# BM833.net
KiCad netlist of a schematic drawn in EAGLE
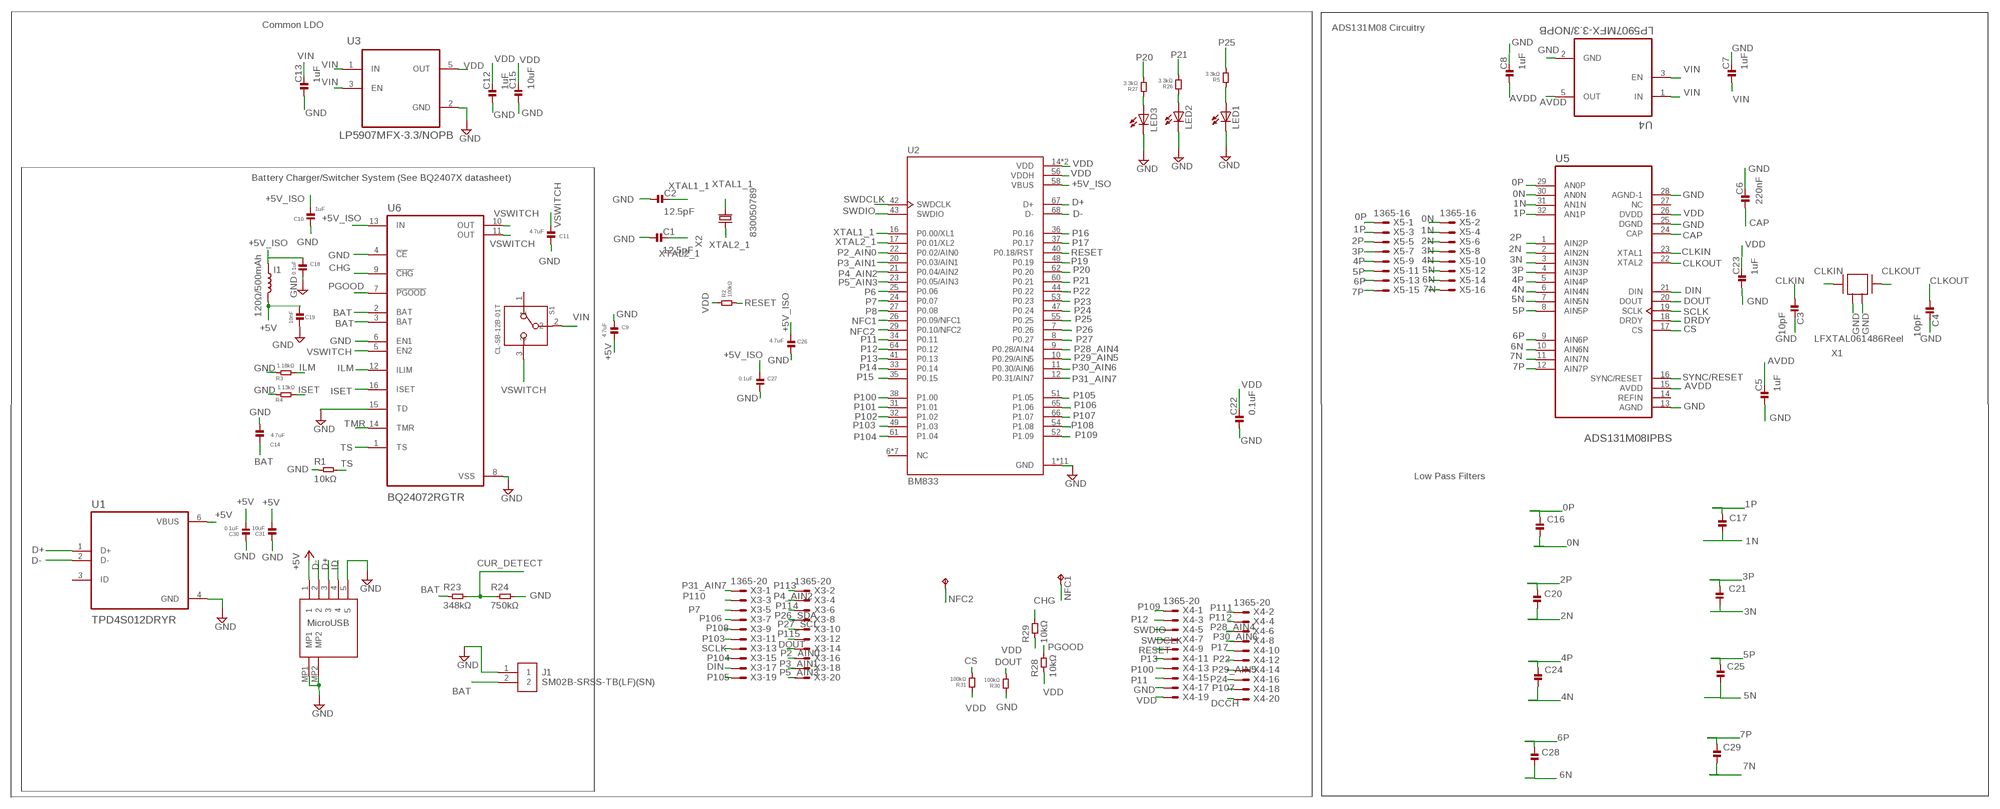
[diagram p0: schematic, sheet 1]

(export (version "E")
  (design (tool "Eeschema 10.0.6"))
  (components
    (comp (ref "C1")
      (value "12.5pF")
      (footprint "eagle-import:0201")
      (libsource (lib "eagle-import") (part "CAPACITOR.0201"))
    )
    (comp (ref "C2")
      (value "12.5pF")
      (footprint "eagle-import:0201")
      (libsource (lib "eagle-import") (part "CAPACITOR.0201"))
    )
    (comp (ref "C3")
      (value "10pF")
      (footprint "eagle-import:0201")
      (libsource (lib "eagle-import") (part "CAPACITOR.0201"))
    )
    (comp (ref "C4")
      (value "10pF")
      (footprint "eagle-import:0201")
      (libsource (lib "eagle-import") (part "CAPACITOR.0201"))
    )
    (comp (ref "C5")
      (value "1uF")
      (footprint "eagle-import:0201")
      (libsource (lib "eagle-import") (part "CAPACITOR.0201"))
    )
    (comp (ref "C6")
      (value "220nF")
      (footprint "eagle-import:0201")
      (libsource (lib "eagle-import") (part "CAPACITOR.0201"))
    )
    (comp (ref "C7")
      (value "1uF")
      (footprint "eagle-import:0201")
      (libsource (lib "eagle-import") (part "CAPACITOR.0201"))
    )
    (comp (ref "C8")
      (value "1uF")
      (footprint "eagle-import:0201")
      (libsource (lib "eagle-import") (part "CAPACITOR.0201"))
    )
    (comp (ref "C9")
      (value "4.7uF")
      (footprint "eagle-import:0201")
      (libsource (lib "eagle-import") (part "CAPACITOR.0201"))
    )
    (comp (ref "C10")
      (value "1uF")
      (footprint "eagle-import:0201")
      (libsource (lib "eagle-import") (part "CAPACITOR.0201"))
    )
    (comp (ref "C11")
      (value "4.7uF")
      (footprint "eagle-import:0201")
      (libsource (lib "eagle-import") (part "CAPACITOR.0201"))
    )
    (comp (ref "C12")
      (value "1uF")
      (footprint "eagle-import:0201")
      (libsource (lib "eagle-import") (part "CAPACITOR.0201"))
    )
    (comp (ref "C13")
      (value "1uF")
      (footprint "eagle-import:0201")
      (libsource (lib "eagle-import") (part "CAPACITOR.0201"))
    )
    (comp (ref "C14")
      (value "4.7uF")
      (footprint "eagle-import:0201")
      (libsource (lib "eagle-import") (part "CAPACITOR.0201"))
    )
    (comp (ref "C15")
      (value "10uF")
      (footprint "eagle-import:0402")
      (libsource (lib "eagle-import") (part "CAPACITOR.0402"))
    )
    (comp (ref "C16")
      (value "100pF")
      (footprint "eagle-import:0201")
      (libsource (lib "eagle-import") (part "CAPACITOR.0201"))
    )
    (comp (ref "C17")
      (value "100pF")
      (footprint "eagle-import:0201")
      (libsource (lib "eagle-import") (part "CAPACITOR.0201"))
    )
    (comp (ref "C18")
      (value "0.1uF")
      (footprint "eagle-import:0201")
      (libsource (lib "eagle-import") (part "CAPACITOR.0201"))
    )
    (comp (ref "C19")
      (value "10nF")
      (footprint "eagle-import:0201")
      (libsource (lib "eagle-import") (part "CAPACITOR.0201"))
    )
    (comp (ref "C20")
      (value "100pF")
      (footprint "eagle-import:0201")
      (libsource (lib "eagle-import") (part "CAPACITOR.0201"))
    )
    (comp (ref "C21")
      (value "100pF")
      (footprint "eagle-import:0201")
      (libsource (lib "eagle-import") (part "CAPACITOR.0201"))
    )
    (comp (ref "C22")
      (value "0.1uF")
      (footprint "eagle-import:0201")
      (libsource (lib "eagle-import") (part "CAPACITOR.0201"))
    )
    (comp (ref "C23")
      (value "1uF")
      (footprint "eagle-import:0201")
      (libsource (lib "eagle-import") (part "CAPACITOR.0201"))
    )
    (comp (ref "C24")
      (value "100pF")
      (footprint "eagle-import:0201")
      (libsource (lib "eagle-import") (part "CAPACITOR.0201"))
    )
    (comp (ref "C25")
      (value "100pF")
      (footprint "eagle-import:0201")
      (libsource (lib "eagle-import") (part "CAPACITOR.0201"))
    )
    (comp (ref "C26")
      (value "4.7uF")
      (footprint "eagle-import:0201")
      (libsource (lib "eagle-import") (part "CAPACITOR.0201"))
    )
    (comp (ref "C27")
      (value "0.1uF")
      (footprint "eagle-import:0201")
      (libsource (lib "eagle-import") (part "CAPACITOR.0201"))
    )
    (comp (ref "C28")
      (value "100pF")
      (footprint "eagle-import:0201")
      (libsource (lib "eagle-import") (part "CAPACITOR.0201"))
    )
    (comp (ref "C29")
      (value "100pF")
      (footprint "eagle-import:0201")
      (libsource (lib "eagle-import") (part "CAPACITOR.0201"))
    )
    (comp (ref "C30")
      (value "0.1uF")
      (footprint "eagle-import:0201")
      (libsource (lib "eagle-import") (part "CAPACITOR.0201"))
    )
    (comp (ref "C31")
      (value "10uF")
      (footprint "eagle-import:0402")
      (libsource (lib "eagle-import") (part "CAPACITOR.0402"))
    )
    (comp (ref "I1")
      (value "120Ω/500mAh")
      (footprint "eagle-import:0402_COILCRAFT")
      (fields (field (name "MOUSER_PART") "994-0402HP-12NXGLU"))
      (libsource (lib "eagle-import") (part "12NH-0402"))
    )
    (comp (ref "J1")
      (value "SM02B-SRSS-TB(LF)(SN)")
      (footprint "eagle-import:SM02B-SRSS-TB(LF)(SN)")
      (fields (field (name "MF") "JST Sales"))
      (libsource (lib "eagle-import") (part "SM02B-SRSS-TB(LF)(SN)"))
    )
    (comp (ref "LED1")
      (value "LEDCHIPLED_0603")
      (footprint "eagle-import:CHIPLED_0603")
      (libsource (lib "eagle-import") (part "LEDCHIPLED_0603"))
    )
    (comp (ref "LED2")
      (value "LEDCHIPLED_0603")
      (footprint "eagle-import:CHIPLED_0603")
      (libsource (lib "eagle-import") (part "LEDCHIPLED_0603"))
    )
    (comp (ref "LED3")
      (value "LEDCHIPLED_0603")
      (footprint "eagle-import:CHIPLED_0603")
      (libsource (lib "eagle-import") (part "LEDCHIPLED_0603"))
    )
    (comp (ref "NFC1")
      (value "TPTP14SQ")
      (footprint "eagle-import:TP14SQ")
      (libsource (lib "eagle-import") (part "TPTP14SQ"))
    )
    (comp (ref "NFC2")
      (value "TPTP14SQ")
      (footprint "eagle-import:TP14SQ")
      (libsource (lib "eagle-import") (part "TPTP14SQ"))
    )
    (comp (ref "R1")
      (value "10kΩ")
      (footprint "eagle-import:0201")
      (libsource (lib "eagle-import") (part "RESISTOR.0201"))
    )
    (comp (ref "R2")
      (value "100kΩ")
      (footprint "eagle-import:0201")
      (libsource (lib "eagle-import") (part "RESISTOR.0201"))
    )
    (comp (ref "R3")
      (value "1.18kΩ")
      (footprint "eagle-import:0201")
      (fields (field (name "SPICEPREFIX") "R"))
      (libsource (lib "eagle-import") (part "RESISTOR.0201"))
    )
    (comp (ref "R4")
      (value "1.13kΩ")
      (footprint "eagle-import:0201")
      (libsource (lib "eagle-import") (part "RESISTOR.0201"))
    )
    (comp (ref "R5")
      (value "3.3kΩ")
      (footprint "eagle-import:0201")
      (libsource (lib "eagle-import") (part "RESISTOR.0201"))
    )
    (comp (ref "R23")
      (value "348kΩ")
      (footprint "eagle-import:0201")
      (libsource (lib "eagle-import") (part "RESISTOR.0201"))
    )
    (comp (ref "R24")
      (value "750kΩ")
      (footprint "eagle-import:0201")
      (libsource (lib "eagle-import") (part "RESISTOR.0201"))
    )
    (comp (ref "R26")
      (value "3.3kΩ")
      (footprint "eagle-import:0201")
      (libsource (lib "eagle-import") (part "RESISTOR.0201"))
    )
    (comp (ref "R27")
      (value "3.3kΩ")
      (footprint "eagle-import:0201")
      (libsource (lib "eagle-import") (part "RESISTOR.0201"))
    )
    (comp (ref "R28")
      (value "10kΩ")
      (footprint "eagle-import:0402")
      (libsource (lib "eagle-import") (part "RESISTOR.0402"))
    )
    (comp (ref "R29")
      (value "10kΩ")
      (footprint "eagle-import:0402")
      (libsource (lib "eagle-import") (part "RESISTOR.0402"))
    )
    (comp (ref "R30")
      (value "100kΩ")
      (footprint "eagle-import:0402")
      (libsource (lib "eagle-import") (part "RESISTOR.0402"))
    )
    (comp (ref "R31")
      (value "100kΩ")
      (footprint "eagle-import:0402")
      (libsource (lib "eagle-import") (part "RESISTOR.0402"))
    )
    (comp (ref "S1")
      (value "CL-SB-12B-01T")
      (footprint "eagle-import:CL-SB-12B")
      (fields (field (name "MF") "Nidec Copal"))
      (libsource (lib "eagle-import") (part "CL-SB-12B-01T"))
    )
    (comp (ref "U1")
      (value "TPD4S012DRYR")
      (footprint "eagle-import:PSON50P145X100X60-6N")
      (fields (field (name "MF") "Texas Instruments"))
      (libsource (lib "eagle-import") (part "TPD4S012DRYR"))
    )
    (comp (ref "U2")
      (value "BM833")
      (footprint "eagle-import:XCVR_BM833")
      (fields (field (name "MF") "Fanstel"))
      (libsource (lib "eagle-import") (part "BM833"))
    )
    (comp (ref "U3")
      (value "LP5907MFX-3.3/NOPB")
      (footprint "eagle-import:SOT95P280X145-5N")
      (fields (field (name "MF") "Texas Instruments"))
      (libsource (lib "eagle-import") (part "LP5907MFX-3.3/NOPB"))
    )
    (comp (ref "U4")
      (value "LP5907MFX-3.3/NOPB")
      (footprint "eagle-import:SOT95P280X145-5N")
      (fields (field (name "MF") "Texas Instruments"))
      (libsource (lib "eagle-import") (part "LP5907MFX-3.3/NOPB"))
    )
    (comp (ref "U5")
      (value "ADS131M08IPBS")
      (footprint "eagle-import:QFP50P700X700X120-32N")
      (fields (field (name "MF") "Texas Instruments"))
      (libsource (lib "eagle-import") (part "ADS131M08IPBS"))
    )
    (comp (ref "U6")
      (value "BQ24072RGTR")
      (footprint "eagle-import:QFN50P300X300X100-17N")
      (fields (field (name "MF") "Texas Instruments"))
      (libsource (lib "eagle-import") (part "BQ24072RGTR"))
    )
    (comp (ref "U7")
      (value "DX4R005JJ2R1800")
      (footprint "eagle-import:DX4R005JJ2R1800")
      (fields (field (name "MF") "JAE Electronics"))
      (libsource (lib "eagle-import") (part "DX4R005JJ2R1800"))
    )
    (comp (ref "X1")
      (value "ABM3B-8.000MHZ-B2-T")
      (footprint "eagle-import:ABM3B-8.000MHZ-B2-T")
      (fields
        (field (name "DIGIKEY_PART_NUMBER") "535-9720-2-ND")
        (field (name "MANUFACTURER") "Abracon LLC")
        (field (name "CREATED_BY") "PCBLayout.com")
      )
      (libsource (lib "eagle-import") (part "ABM3B-8.000MHZ-B2-T"))
    )
    (comp (ref "X2")
      (value "FC-12M")
      (footprint "eagle-import:FC-12M")
      (libsource (lib "eagle-import") (part "FC-12M"))
    )
    (comp (ref "X3")
      (value "1365-20")
      (footprint "eagle-import:1365-20")
      (libsource (lib "eagle-import") (part "1365-20"))
    )
    (comp (ref "X4")
      (value "1365-20")
      (footprint "eagle-import:1365-20")
      (libsource (lib "eagle-import") (part "1365-20"))
    )
    (comp (ref "X5")
      (value "1365-16")
      (footprint "eagle-import:1365-16")
      (libsource (lib "eagle-import") (part "1365-16"))
    )
  )
  (nets
    (net (code "1") (name "+5V") (class "Default")
      (node (ref "C19") (pin "2") (pinfunction "2_2") (pintype "bidirectional"))
      (node (ref "C30") (pin "2") (pinfunction "2_2") (pintype "bidirectional"))
      (node (ref "C31") (pin "2") (pinfunction "2_2") (pintype "bidirectional"))
      (node (ref "C9") (pin "2") (pinfunction "2_2") (pintype "bidirectional"))
      (node (ref "I1") (pin "P$2") (pinfunction "2_P$2") (pintype "passive"))
      (node (ref "U1") (pin "6") (pinfunction "VBUS_6") (pintype "power_in"))
      (node (ref "U7") (pin "1") (pinfunction "1_1") (pintype "bidirectional"))
    )
    (net (code "2") (name "+5V_ISO") (class "Default")
      (node (ref "C10") (pin "2") (pinfunction "2_2") (pintype "bidirectional"))
      (node (ref "C18") (pin "1") (pinfunction "1_1") (pintype "bidirectional"))
      (node (ref "C26") (pin "2") (pinfunction "2_2") (pintype "bidirectional"))
      (node (ref "C27") (pin "2") (pinfunction "2_2") (pintype "bidirectional"))
      (node (ref "I1") (pin "P$1") (pinfunction "1_P$1") (pintype "passive"))
      (node (ref "U2") (pin "58") (pinfunction "VBUS_58") (pintype "power_in"))
      (node (ref "U6") (pin "13") (pinfunction "IN_13") (pintype "input"))
    )
    (net (code "3") (name "0N") (class "Default")
      (node (ref "C16") (pin "2") (pinfunction "2_2") (pintype "bidirectional"))
      (node (ref "U5") (pin "30") (pinfunction "AN0N_30") (pintype "bidirectional"))
      (node (ref "X5") (pin "2") (pinfunction "S_2") (pintype "passive"))
    )
    (net (code "4") (name "0P") (class "Default")
      (node (ref "C16") (pin "1") (pinfunction "1_1") (pintype "bidirectional"))
      (node (ref "U5") (pin "29") (pinfunction "AN0P_29") (pintype "bidirectional"))
      (node (ref "X5") (pin "1") (pinfunction "S_1") (pintype "passive"))
    )
    (net (code "5") (name "1N") (class "Default")
      (node (ref "C17") (pin "2") (pinfunction "2_2") (pintype "bidirectional"))
      (node (ref "U5") (pin "31") (pinfunction "AN1N_31") (pintype "bidirectional"))
      (node (ref "X5") (pin "4") (pinfunction "S_4") (pintype "passive"))
    )
    (net (code "6") (name "1P") (class "Default")
      (node (ref "C17") (pin "1") (pinfunction "1_1") (pintype "bidirectional"))
      (node (ref "U5") (pin "32") (pinfunction "AN1P_32") (pintype "bidirectional"))
      (node (ref "X5") (pin "3") (pinfunction "S_3") (pintype "passive"))
    )
    (net (code "7") (name "2N") (class "Default")
      (node (ref "C20") (pin "2") (pinfunction "2_2") (pintype "bidirectional"))
      (node (ref "U5") (pin "2") (pinfunction "AIN2N_2") (pintype "input"))
      (node (ref "X5") (pin "6") (pinfunction "S_6") (pintype "passive"))
    )
    (net (code "8") (name "2P") (class "Default")
      (node (ref "C20") (pin "1") (pinfunction "1_1") (pintype "bidirectional"))
      (node (ref "U5") (pin "1") (pinfunction "AIN2P_1") (pintype "input"))
      (node (ref "X5") (pin "5") (pinfunction "S_5") (pintype "passive"))
    )
    (net (code "9") (name "3N") (class "Default")
      (node (ref "C21") (pin "2") (pinfunction "2_2") (pintype "bidirectional"))
      (node (ref "U5") (pin "3") (pinfunction "AIN3N_3") (pintype "input"))
      (node (ref "X5") (pin "8") (pinfunction "S_8") (pintype "passive"))
    )
    (net (code "10") (name "3P") (class "Default")
      (node (ref "C21") (pin "1") (pinfunction "1_1") (pintype "bidirectional"))
      (node (ref "U5") (pin "4") (pinfunction "AIN3P_4") (pintype "input"))
      (node (ref "X5") (pin "7") (pinfunction "S_7") (pintype "passive"))
    )
    (net (code "11") (name "4N") (class "Default")
      (node (ref "C24") (pin "2") (pinfunction "2_2") (pintype "bidirectional"))
      (node (ref "U5") (pin "6") (pinfunction "AIN4N_6") (pintype "input"))
      (node (ref "X5") (pin "10") (pinfunction "S_10") (pintype "passive"))
    )
    (net (code "12") (name "4P") (class "Default")
      (node (ref "C24") (pin "1") (pinfunction "1_1") (pintype "bidirectional"))
      (node (ref "U5") (pin "5") (pinfunction "AIN4P_5") (pintype "input"))
      (node (ref "X5") (pin "9") (pinfunction "S_9") (pintype "passive"))
    )
    (net (code "13") (name "5N") (class "Default")
      (node (ref "C25") (pin "2") (pinfunction "2_2") (pintype "bidirectional"))
      (node (ref "U5") (pin "7") (pinfunction "AIN5N_7") (pintype "input"))
      (node (ref "X5") (pin "12") (pinfunction "S_12") (pintype "passive"))
    )
    (net (code "14") (name "5P") (class "Default")
      (node (ref "C25") (pin "1") (pinfunction "1_1") (pintype "bidirectional"))
      (node (ref "U5") (pin "8") (pinfunction "AIN5P_8") (pintype "input"))
      (node (ref "X5") (pin "11") (pinfunction "S_11") (pintype "passive"))
    )
    (net (code "15") (name "6N") (class "Default")
      (node (ref "C28") (pin "2") (pinfunction "2_2") (pintype "bidirectional"))
      (node (ref "U5") (pin "10") (pinfunction "AIN6N_10") (pintype "input"))
      (node (ref "X5") (pin "14") (pinfunction "S_14") (pintype "passive"))
    )
    (net (code "16") (name "6P") (class "Default")
      (node (ref "C28") (pin "1") (pinfunction "1_1") (pintype "bidirectional"))
      (node (ref "U5") (pin "9") (pinfunction "AIN6P_9") (pintype "input"))
      (node (ref "X5") (pin "13") (pinfunction "S_13") (pintype "passive"))
    )
    (net (code "17") (name "7N") (class "Default")
      (node (ref "C29") (pin "2") (pinfunction "2_2") (pintype "bidirectional"))
      (node (ref "U5") (pin "11") (pinfunction "AIN7N_11") (pintype "input"))
      (node (ref "X5") (pin "16") (pinfunction "S_16") (pintype "passive"))
    )
    (net (code "18") (name "7P") (class "Default")
      (node (ref "C29") (pin "1") (pinfunction "1_1") (pintype "bidirectional"))
      (node (ref "U5") (pin "12") (pinfunction "AIN7P_12") (pintype "input"))
      (node (ref "X5") (pin "15") (pinfunction "S_15") (pintype "passive"))
    )
    (net (code "19") (name "AVDD") (class "Default")
      (node (ref "C5") (pin "2") (pinfunction "2_2") (pintype "bidirectional"))
      (node (ref "C8") (pin "1") (pinfunction "1_1") (pintype "bidirectional"))
      (node (ref "U4") (pin "5") (pinfunction "OUT_5") (pintype "output"))
      (node (ref "U5") (pin "15") (pinfunction "AVDD_15") (pintype "power_in"))
    )
    (net (code "20") (name "BAT") (class "Default")
      (node (ref "C14") (pin "2") (pinfunction "2_2") (pintype "bidirectional"))
      (node (ref "J1") (pin "2") (pinfunction "2_2") (pintype "bidirectional"))
      (node (ref "R23") (pin "1") (pinfunction "1_1") (pintype "bidirectional"))
      (node (ref "U6") (pin "2") (pinfunction "BAT_2") (pintype "bidirectional"))
      (node (ref "U6") (pin "3") (pinfunction "BAT_3") (pintype "bidirectional"))
    )
    (net (code "21") (name "CAP") (class "Default")
      (node (ref "C6") (pin "1") (pinfunction "1_1") (pintype "bidirectional"))
      (node (ref "U5") (pin "24") (pinfunction "CAP_24") (pintype "bidirectional"))
    )
    (net (code "22") (name "CHG") (class "Default")
      (node (ref "R29") (pin "2") (pinfunction "2_2") (pintype "bidirectional"))
      (node (ref "U6") (pin "9") (pinfunction "~{CHG}_9") (pintype "bidirectional"))
    )
    (net (code "23") (name "CLKIN") (class "Default")
      (node (ref "C3") (pin "1") (pinfunction "1_1") (pintype "bidirectional"))
      (node (ref "U5") (pin "23") (pinfunction "XTAL1_23") (pintype "bidirectional"))
      (node (ref "X1") (pin "1") (pinfunction "1_1") (pintype "passive"))
    )
    (net (code "24") (name "CLKOUT") (class "Default")
      (node (ref "C4") (pin "1") (pinfunction "1_1") (pintype "bidirectional"))
      (node (ref "U5") (pin "22") (pinfunction "XTAL2_22") (pintype "bidirectional"))
      (node (ref "X1") (pin "3") (pinfunction "3_3") (pintype "passive"))
    )
    (net (code "25") (name "CS") (class "Default")
      (node (ref "R31") (pin "1") (pinfunction "1_1") (pintype "bidirectional"))
      (node (ref "U5") (pin "17") (pinfunction "CS_17") (pintype "bidirectional"))
    )
    (net (code "26") (name "CUR_DETECT") (class "Default")
      (node (ref "R23") (pin "2") (pinfunction "2_2") (pintype "bidirectional"))
      (node (ref "R24") (pin "1") (pinfunction "1_1") (pintype "bidirectional"))
    )
    (net (code "27") (name "D+") (class "Default")
      (node (ref "U1") (pin "1") (pinfunction "D+_1") (pintype "bidirectional"))
      (node (ref "U2") (pin "67") (pinfunction "D+_67") (pintype "bidirectional"))
      (node (ref "U7") (pin "3") (pinfunction "3_3") (pintype "bidirectional"))
    )
    (net (code "28") (name "D-") (class "Default")
      (node (ref "U1") (pin "2") (pinfunction "D-_2") (pintype "bidirectional"))
      (node (ref "U2") (pin "68") (pinfunction "D-_68") (pintype "bidirectional"))
      (node (ref "U7") (pin "2") (pinfunction "2_2") (pintype "bidirectional"))
    )
    (net (code "29") (name "DCCH") (class "Default")
      (node (ref "X4") (pin "20") (pinfunction "S_20") (pintype "passive"))
    )
    (net (code "30") (name "DIN") (class "Default")
      (node (ref "U5") (pin "21") (pinfunction "DIN_21") (pintype "input"))
      (node (ref "X3") (pin "17") (pinfunction "S_17") (pintype "passive"))
    )
    (net (code "31") (name "DOUT") (class "Default")
      (node (ref "R30") (pin "1") (pinfunction "1_1") (pintype "bidirectional"))
      (node (ref "U5") (pin "20") (pinfunction "DOUT_20") (pintype "output"))
      (node (ref "X3") (pin "14") (pinfunction "S_14") (pintype "passive"))
    )
    (net (code "32") (name "DRDY") (class "Default")
      (node (ref "U5") (pin "18") (pinfunction "DRDY_18") (pintype "output"))
    )
    (net (code "33") (name "GND") (class "Default")
      (node (ref "C1") (pin "1") (pinfunction "1_1") (pintype "bidirectional"))
      (node (ref "C10") (pin "1") (pinfunction "1_1") (pintype "bidirectional"))
      (node (ref "C11") (pin "1") (pinfunction "1_1") (pintype "bidirectional"))
      (node (ref "C12") (pin "1") (pinfunction "1_1") (pintype "bidirectional"))
      (node (ref "C13") (pin "1") (pinfunction "1_1") (pintype "bidirectional"))
      (node (ref "C14") (pin "1") (pinfunction "1_1") (pintype "bidirectional"))
      (node (ref "C15") (pin "1") (pinfunction "1_1") (pintype "bidirectional"))
      (node (ref "C18") (pin "2") (pinfunction "2_2") (pintype "bidirectional"))
      (node (ref "C19") (pin "1") (pinfunction "1_1") (pintype "bidirectional"))
      (node (ref "C2") (pin "1") (pinfunction "1_1") (pintype "bidirectional"))
      (node (ref "C22") (pin "1") (pinfunction "1_1") (pintype "bidirectional"))
      (node (ref "C23") (pin "1") (pinfunction "1_1") (pintype "bidirectional"))
      (node (ref "C26") (pin "1") (pinfunction "1_1") (pintype "bidirectional"))
      (node (ref "C27") (pin "1") (pinfunction "1_1") (pintype "bidirectional"))
      (node (ref "C3") (pin "2") (pinfunction "2_2") (pintype "bidirectional"))
      (node (ref "C30") (pin "1") (pinfunction "1_1") (pintype "bidirectional"))
      (node (ref "C31") (pin "1") (pinfunction "1_1") (pintype "bidirectional"))
      (node (ref "C4") (pin "2") (pinfunction "2_2") (pintype "bidirectional"))
      (node (ref "C5") (pin "1") (pinfunction "1_1") (pintype "bidirectional"))
      (node (ref "C6") (pin "2") (pinfunction "2_2") (pintype "bidirectional"))
      (node (ref "C7") (pin "2") (pinfunction "2_2") (pintype "bidirectional"))
      (node (ref "C8") (pin "2") (pinfunction "2_2") (pintype "bidirectional"))
      (node (ref "C9") (pin "1") (pinfunction "1_1") (pintype "bidirectional"))
      (node (ref "J1") (pin "1") (pinfunction "1_1") (pintype "bidirectional"))
      (node (ref "LED1") (pin "C") (pinfunction "C_C") (pintype "passive"))
      (node (ref "LED2") (pin "C") (pinfunction "C_C") (pintype "passive"))
      (node (ref "LED3") (pin "C") (pinfunction "C_C") (pintype "passive"))
      (node (ref "R1") (pin "1") (pinfunction "1_1") (pintype "bidirectional"))
      (node (ref "R24") (pin "2") (pinfunction "2_2") (pintype "bidirectional"))
      (node (ref "R3") (pin "1") (pinfunction "1_1") (pintype "bidirectional"))
      (node (ref "R30") (pin "2") (pinfunction "2_2") (pintype "bidirectional"))
      (node (ref "R4") (pin "1") (pinfunction "1_1") (pintype "bidirectional"))
      (node (ref "U1") (pin "4") (pinfunction "GND_4") (pintype "power_in"))
      (node (ref "U2") (pin "1") (pinfunction "GND_1") (pintype "power_in"))
      (node (ref "U2") (pin "13") (pinfunction "GND_13") (pintype "power_in"))
      (node (ref "U2") (pin "15") (pinfunction "GND_15") (pintype "power_in"))
      (node (ref "U2") (pin "18") (pinfunction "GND_18") (pintype "power_in"))
      (node (ref "U2") (pin "19") (pinfunction "GND_19") (pintype "power_in"))
      (node (ref "U2") (pin "2") (pinfunction "GND_2") (pintype "power_in"))
      (node (ref "U2") (pin "3") (pinfunction "GND_3") (pintype "power_in"))
      (node (ref "U2") (pin "30") (pinfunction "GND_30") (pintype "power_in"))
      (node (ref "U2") (pin "4") (pinfunction "GND_4") (pintype "power_in"))
      (node (ref "U2") (pin "45") (pinfunction "GND_45") (pintype "power_in"))
      (node (ref "U2") (pin "5") (pinfunction "GND_5") (pintype "power_in"))
      (node (ref "U3") (pin "2") (pinfunction "GND_2") (pintype "power_in"))
      (node (ref "U4") (pin "2") (pinfunction "GND_2") (pintype "power_in"))
      (node (ref "U5") (pin "13") (pinfunction "AGND_13") (pintype "power_in"))
      (node (ref "U5") (pin "25") (pinfunction "DGND_25") (pintype "power_in"))
      (node (ref "U5") (pin "28") (pinfunction "AGND-1_28") (pintype "power_in"))
      (node (ref "U6") (pin "15") (pinfunction "TD_15") (pintype "bidirectional"))
      (node (ref "U6") (pin "4") (pinfunction "~{CE}_4") (pintype "bidirectional"))
      (node (ref "U6") (pin "6") (pinfunction "EN1_6") (pintype "bidirectional"))
      (node (ref "U6") (pin "8") (pinfunction "VSS_8") (pintype "power_in"))
      (node (ref "U7") (pin "5") (pinfunction "5_5") (pintype "bidirectional"))
      (node (ref "U7") (pin "MP1") (pinfunction "MP1_MP1") (pintype "bidirectional"))
      (node (ref "U7") (pin "MP2") (pinfunction "MP2_MP2") (pintype "bidirectional"))
      (node (ref "X1") (pin "2") (pinfunction "2_2") (pintype "passive"))
      (node (ref "X1") (pin "4") (pinfunction "4_4") (pintype "passive"))
      (node (ref "X4") (pin "17") (pinfunction "S_17") (pintype "passive"))
    )
    (net (code "34") (name "ID") (class "Default")
      (node (ref "U7") (pin "4") (pinfunction "4_4") (pintype "bidirectional"))
    )
    (net (code "35") (name "ILM") (class "Default")
      (node (ref "R3") (pin "2") (pinfunction "2_2") (pintype "bidirectional"))
      (node (ref "U6") (pin "12") (pinfunction "ILIM_12") (pintype "bidirectional"))
    )
    (net (code "36") (name "ISET") (class "Default")
      (node (ref "R4") (pin "2") (pinfunction "2_2") (pintype "bidirectional"))
      (node (ref "U6") (pin "16") (pinfunction "ISET_16") (pintype "bidirectional"))
    )
    (net (code "37") (name "NFC1") (class "Default")
      (node (ref "NFC2") (pin "TP") (pinfunction "TP_TP") (pintype "input"))
      (node (ref "U2") (pin "26") (pinfunction "P0.09/NFC1_26") (pintype "bidirectional"))
    )
    (net (code "38") (name "NFC2") (class "Default")
      (node (ref "NFC1") (pin "TP") (pinfunction "TP_TP") (pintype "input"))
      (node (ref "U2") (pin "29") (pinfunction "P0.10/NFC2_29") (pintype "bidirectional"))
    )
    (net (code "39") (name "Net-(LED1-PadA)") (class "Default")
      (node (ref "LED1") (pin "A") (pinfunction "A_A") (pintype "passive"))
      (node (ref "R5") (pin "2") (pinfunction "2_2") (pintype "bidirectional"))
    )
    (net (code "40") (name "Net-(LED2-PadA)") (class "Default")
      (node (ref "LED2") (pin "A") (pinfunction "A_A") (pintype "passive"))
      (node (ref "R26") (pin "2") (pinfunction "2_2") (pintype "bidirectional"))
    )
    (net (code "41") (name "Net-(LED3-PadA)") (class "Default")
      (node (ref "LED3") (pin "A") (pinfunction "A_A") (pintype "passive"))
      (node (ref "R27") (pin "2") (pinfunction "2_2") (pintype "bidirectional"))
    )
    (net (code "42") (name "P2_AIN0") (class "Default")
      (node (ref "U2") (pin "22") (pinfunction "P0.02/AIN0_22") (pintype "bidirectional"))
      (node (ref "X3") (pin "16") (pinfunction "S_16") (pintype "passive"))
    )
    (net (code "43") (name "P3_AIN1") (class "Default")
      (node (ref "U2") (pin "20") (pinfunction "P0.03/AIN1_20") (pintype "bidirectional"))
      (node (ref "X3") (pin "18") (pinfunction "S_18") (pintype "passive"))
    )
    (net (code "44") (name "P4_AIN2") (class "Default")
      (node (ref "U2") (pin "21") (pinfunction "P0.04/AIN2_21") (pintype "bidirectional"))
      (node (ref "X3") (pin "4") (pinfunction "S_4") (pintype "passive"))
    )
    (net (code "45") (name "P5_AIN3") (class "Default")
      (node (ref "U2") (pin "23") (pinfunction "P0.05/AIN3_23") (pintype "bidirectional"))
      (node (ref "X3") (pin "20") (pinfunction "S_20") (pintype "passive"))
    )
    (net (code "46") (name "P6") (class "Default")
      (node (ref "U2") (pin "25") (pinfunction "P0.06_25") (pintype "bidirectional"))
    )
    (net (code "47") (name "P7") (class "Default")
      (node (ref "U2") (pin "24") (pinfunction "P0.07_24") (pintype "bidirectional"))
      (node (ref "X3") (pin "5") (pinfunction "S_5") (pintype "passive"))
    )
    (net (code "48") (name "P8") (class "Default")
      (node (ref "U2") (pin "27") (pinfunction "P0.08_27") (pintype "bidirectional"))
    )
    (net (code "49") (name "P11") (class "Default")
      (node (ref "U2") (pin "34") (pinfunction "P0.11_34") (pintype "bidirectional"))
      (node (ref "X4") (pin "15") (pinfunction "S_15") (pintype "passive"))
    )
    (net (code "50") (name "P12") (class "Default")
      (node (ref "U2") (pin "64") (pinfunction "P0.12_64") (pintype "bidirectional"))
      (node (ref "X4") (pin "3") (pinfunction "S_3") (pintype "passive"))
    )
    (net (code "51") (name "P13") (class "Default")
      (node (ref "U2") (pin "41") (pinfunction "P0.13_41") (pintype "bidirectional"))
      (node (ref "X4") (pin "11") (pinfunction "S_11") (pintype "passive"))
    )
    (net (code "52") (name "P14") (class "Default")
      (node (ref "U2") (pin "33") (pinfunction "P0.14_33") (pintype "bidirectional"))
    )
    (net (code "53") (name "P15") (class "Default")
      (node (ref "U2") (pin "35") (pinfunction "P0.15_35") (pintype "bidirectional"))
    )
    (net (code "54") (name "P16") (class "Default")
      (node (ref "U2") (pin "36") (pinfunction "P0.16_36") (pintype "bidirectional"))
    )
    (net (code "55") (name "P17") (class "Default")
      (node (ref "U2") (pin "37") (pinfunction "P0.17_37") (pintype "bidirectional"))
      (node (ref "X4") (pin "10") (pinfunction "S_10") (pintype "passive"))
    )
    (net (code "56") (name "P19") (class "Default")
      (node (ref "U2") (pin "48") (pinfunction "P0.19_48") (pintype "bidirectional"))
    )
    (net (code "57") (name "P20") (class "Default")
      (node (ref "R27") (pin "1") (pinfunction "1_1") (pintype "bidirectional"))
      (node (ref "U2") (pin "62") (pinfunction "P0.20_62") (pintype "bidirectional"))
    )
    (net (code "58") (name "P21") (class "Default")
      (node (ref "R26") (pin "1") (pinfunction "1_1") (pintype "bidirectional"))
      (node (ref "U2") (pin "60") (pinfunction "P0.21_60") (pintype "bidirectional"))
    )
    (net (code "59") (name "P22") (class "Default")
      (node (ref "U2") (pin "44") (pinfunction "P0.22_44") (pintype "bidirectional"))
      (node (ref "X4") (pin "12") (pinfunction "S_12") (pintype "passive"))
    )
    (net (code "60") (name "P23") (class "Default")
      (node (ref "U2") (pin "53") (pinfunction "P0.23_53") (pintype "bidirectional"))
    )
    (net (code "61") (name "P24") (class "Default")
      (node (ref "U2") (pin "47") (pinfunction "P0.24_47") (pintype "bidirectional"))
      (node (ref "X4") (pin "16") (pinfunction "S_16") (pintype "passive"))
    )
    (net (code "62") (name "P25") (class "Default")
      (node (ref "R5") (pin "1") (pinfunction "1_1") (pintype "bidirectional"))
      (node (ref "U2") (pin "55") (pinfunction "P0.25_55") (pintype "bidirectional"))
    )
    (net (code "63") (name "P26") (class "Default")
      (node (ref "U2") (pin "7") (pinfunction "P0.26_7") (pintype "bidirectional"))
    )
    (net (code "64") (name "P26_SDA") (class "Default")
      (node (ref "X3") (pin "8") (pinfunction "S_8") (pintype "passive"))
    )
    (net (code "65") (name "P27") (class "Default")
      (node (ref "U2") (pin "8") (pinfunction "P0.27_8") (pintype "bidirectional"))
    )
    (net (code "66") (name "P27_SCL") (class "Default")
      (node (ref "X3") (pin "10") (pinfunction "S_10") (pintype "passive"))
    )
    (net (code "67") (name "P28_AIN4") (class "Default")
      (node (ref "U2") (pin "9") (pinfunction "P0.28/AIN4_9") (pintype "bidirectional"))
      (node (ref "X4") (pin "6") (pinfunction "S_6") (pintype "passive"))
    )
    (net (code "68") (name "P29_AIN5") (class "Default")
      (node (ref "U2") (pin "10") (pinfunction "P0.29/AIN5_10") (pintype "bidirectional"))
      (node (ref "X4") (pin "14") (pinfunction "S_14") (pintype "passive"))
    )
    (net (code "69") (name "P30_AIN6") (class "Default")
      (node (ref "U2") (pin "11") (pinfunction "P0.30/AIN6_11") (pintype "bidirectional"))
      (node (ref "X4") (pin "8") (pinfunction "S_8") (pintype "passive"))
    )
    (net (code "70") (name "P31_AIN7") (class "Default")
      (node (ref "U2") (pin "12") (pinfunction "P0.31/AIN7_12") (pintype "bidirectional"))
      (node (ref "X3") (pin "1") (pinfunction "S_1") (pintype "passive"))
    )
    (net (code "71") (name "P100") (class "Default")
      (node (ref "U2") (pin "38") (pinfunction "P1.00_38") (pintype "bidirectional"))
      (node (ref "X4") (pin "13") (pinfunction "S_13") (pintype "passive"))
    )
    (net (code "72") (name "P101") (class "Default")
      (node (ref "U2") (pin "31") (pinfunction "P1.01_31") (pintype "bidirectional"))
    )
    (net (code "73") (name "P102") (class "Default")
      (node (ref "U2") (pin "32") (pinfunction "P1.02_32") (pintype "bidirectional"))
    )
    (net (code "74") (name "P103") (class "Default")
      (node (ref "U2") (pin "49") (pinfunction "P1.03_49") (pintype "bidirectional"))
      (node (ref "X3") (pin "11") (pinfunction "S_11") (pintype "passive"))
    )
    (net (code "75") (name "P104") (class "Default")
      (node (ref "U2") (pin "61") (pinfunction "P1.04_61") (pintype "bidirectional"))
      (node (ref "X3") (pin "15") (pinfunction "S_15") (pintype "passive"))
    )
    (net (code "76") (name "P105") (class "Default")
      (node (ref "U2") (pin "51") (pinfunction "P1.05_51") (pintype "bidirectional"))
      (node (ref "X3") (pin "19") (pinfunction "S_19") (pintype "passive"))
    )
    (net (code "77") (name "P106") (class "Default")
      (node (ref "U2") (pin "65") (pinfunction "P1.06_65") (pintype "bidirectional"))
      (node (ref "X3") (pin "7") (pinfunction "S_7") (pintype "passive"))
    )
    (net (code "78") (name "P107") (class "Default")
      (node (ref "U2") (pin "66") (pinfunction "P1.07_66") (pintype "bidirectional"))
      (node (ref "X4") (pin "18") (pinfunction "S_18") (pintype "passive"))
    )
    (net (code "79") (name "P108") (class "Default")
      (node (ref "U2") (pin "54") (pinfunction "P1.08_54") (pintype "bidirectional"))
      (node (ref "X3") (pin "9") (pinfunction "S_9") (pintype "passive"))
    )
    (net (code "80") (name "P109") (class "Default")
      (node (ref "U2") (pin "52") (pinfunction "P1.09_52") (pintype "bidirectional"))
      (node (ref "X4") (pin "1") (pinfunction "S_1") (pintype "passive"))
    )
    (net (code "81") (name "P110") (class "Default")
      (node (ref "X3") (pin "3") (pinfunction "S_3") (pintype "passive"))
    )
    (net (code "82") (name "P111") (class "Default")
      (node (ref "X4") (pin "2") (pinfunction "S_2") (pintype "passive"))
    )
    (net (code "83") (name "P112") (class "Default")
      (node (ref "X4") (pin "4") (pinfunction "S_4") (pintype "passive"))
    )
    (net (code "84") (name "P113") (class "Default")
      (node (ref "X3") (pin "2") (pinfunction "S_2") (pintype "passive"))
    )
    (net (code "85") (name "P114") (class "Default")
      (node (ref "X3") (pin "6") (pinfunction "S_6") (pintype "passive"))
    )
    (net (code "86") (name "P115") (class "Default")
      (node (ref "X3") (pin "12") (pinfunction "S_12") (pintype "passive"))
    )
    (net (code "87") (name "PGOOD") (class "Default")
      (node (ref "R28") (pin "2") (pinfunction "2_2") (pintype "bidirectional"))
      (node (ref "U6") (pin "7") (pinfunction "~{PGOOD}_7") (pintype "bidirectional"))
    )
    (net (code "88") (name "RESET") (class "Default")
      (node (ref "R2") (pin "1") (pinfunction "1_1") (pintype "bidirectional"))
      (node (ref "U2") (pin "40") (pinfunction "P0.18/RST_40") (pintype "bidirectional"))
      (node (ref "X4") (pin "9") (pinfunction "S_9") (pintype "passive"))
    )
    (net (code "89") (name "SCLK") (class "Default")
      (node (ref "U5") (pin "19") (pinfunction "SCLK_19") (pintype "input"))
      (node (ref "X3") (pin "13") (pinfunction "S_13") (pintype "passive"))
    )
    (net (code "90") (name "SWDCLK") (class "Default")
      (node (ref "U2") (pin "42") (pinfunction "SWDCLK_42") (pintype "input"))
      (node (ref "X4") (pin "7") (pinfunction "S_7") (pintype "passive"))
    )
    (net (code "91") (name "SWDIO") (class "Default")
      (node (ref "U2") (pin "43") (pinfunction "SWDIO_43") (pintype "bidirectional"))
      (node (ref "X4") (pin "5") (pinfunction "S_5") (pintype "passive"))
    )
    (net (code "92") (name "SYNC{slash}RESET") (class "Default")
      (node (ref "U5") (pin "16") (pinfunction "SYNC/RESET_16") (pintype "bidirectional"))
    )
    (net (code "93") (name "TMR") (class "Default")
      (node (ref "U6") (pin "14") (pinfunction "TMR_14") (pintype "bidirectional"))
    )
    (net (code "94") (name "TS") (class "Default")
      (node (ref "R1") (pin "2") (pinfunction "2_2") (pintype "bidirectional"))
      (node (ref "U6") (pin "1") (pinfunction "TS_1") (pintype "bidirectional"))
    )
    (net (code "95") (name "VDD") (class "Default")
      (node (ref "C12") (pin "2") (pinfunction "2_2") (pintype "bidirectional"))
      (node (ref "C15") (pin "2") (pinfunction "2_2") (pintype "bidirectional"))
      (node (ref "C22") (pin "2") (pinfunction "2_2") (pintype "bidirectional"))
      (node (ref "C23") (pin "2") (pinfunction "2_2") (pintype "bidirectional"))
      (node (ref "R2") (pin "2") (pinfunction "2_2") (pintype "bidirectional"))
      (node (ref "R28") (pin "1") (pinfunction "1_1") (pintype "bidirectional"))
      (node (ref "R29") (pin "1") (pinfunction "1_1") (pintype "bidirectional"))
      (node (ref "R31") (pin "2") (pinfunction "2_2") (pintype "bidirectional"))
      (node (ref "U2") (pin "14") (pinfunction "VDD_14") (pintype "power_in"))
      (node (ref "U2") (pin "28") (pinfunction "VDD_28") (pintype "power_in"))
      (node (ref "U2") (pin "56") (pinfunction "VDDH_56") (pintype "power_in"))
      (node (ref "U3") (pin "5") (pinfunction "OUT_5") (pintype "output"))
      (node (ref "U5") (pin "26") (pinfunction "DVDD_26") (pintype "power_in"))
      (node (ref "X4") (pin "19") (pinfunction "S_19") (pintype "passive"))
    )
    (net (code "96") (name "VIN") (class "Default")
      (node (ref "C13") (pin "2") (pinfunction "2_2") (pintype "bidirectional"))
      (node (ref "C7") (pin "1") (pinfunction "1_1") (pintype "bidirectional"))
      (node (ref "S1") (pin "2") (pinfunction "2_2") (pintype "bidirectional"))
      (node (ref "U3") (pin "1") (pinfunction "IN_1") (pintype "input"))
      (node (ref "U3") (pin "3") (pinfunction "EN_3") (pintype "input"))
      (node (ref "U4") (pin "1") (pinfunction "IN_1") (pintype "input"))
      (node (ref "U4") (pin "3") (pinfunction "EN_3") (pintype "input"))
    )
    (net (code "97") (name "VSWITCH") (class "Default")
      (node (ref "C11") (pin "2") (pinfunction "2_2") (pintype "bidirectional"))
      (node (ref "S1") (pin "3") (pinfunction "3_3") (pintype "bidirectional"))
      (node (ref "U6") (pin "10") (pinfunction "OUT_10") (pintype "output"))
      (node (ref "U6") (pin "11") (pinfunction "OUT_11") (pintype "output"))
      (node (ref "U6") (pin "5") (pinfunction "EN2_5") (pintype "bidirectional"))
    )
    (net (code "98") (name "XTAL1_1") (class "Default")
      (node (ref "C2") (pin "2") (pinfunction "2_2") (pintype "bidirectional"))
      (node (ref "U2") (pin "16") (pinfunction "P0.00/XL1_16") (pintype "bidirectional"))
      (node (ref "X2") (pin "2") (pinfunction "2_2") (pintype "passive"))
    )
    (net (code "99") (name "XTAL2_1") (class "Default")
      (node (ref "C1") (pin "2") (pinfunction "2_2") (pintype "bidirectional"))
      (node (ref "U2") (pin "17") (pinfunction "P0.01/XL2_17") (pintype "bidirectional"))
      (node (ref "X2") (pin "1") (pinfunction "1_1") (pintype "passive"))
    )
    (net (code "100") (name "unconnected-(S1-Pad1)") (class "Default")
      (node (ref "S1") (pin "1") (pinfunction "1_1") (pintype "bidirectional"))
    )
    (net (code "101") (name "unconnected-(U1-ID-Pad3)") (class "Default")
      (node (ref "U1") (pin "3") (pinfunction "ID_3") (pintype "bidirectional"))
    )
    (net (code "102") (name "unconnected-(U2-NC-Pad6)") (class "Default")
      (node (ref "U2") (pin "6") (pinfunction "NC_6") (pintype "no_connect"))
    )
    (net (code "103") (name "unconnected-(U2-NC-Pad39)") (class "Default")
      (node (ref "U2") (pin "39") (pinfunction "NC_39") (pintype "no_connect"))
    )
    (net (code "104") (name "unconnected-(U2-NC-Pad46)") (class "Default")
      (node (ref "U2") (pin "46") (pinfunction "NC_46") (pintype "no_connect"))
    )
    (net (code "105") (name "unconnected-(U2-NC-Pad50)") (class "Default")
      (node (ref "U2") (pin "50") (pinfunction "NC_50") (pintype "no_connect"))
    )
    (net (code "106") (name "unconnected-(U2-NC-Pad57)") (class "Default")
      (node (ref "U2") (pin "57") (pinfunction "NC_57") (pintype "no_connect"))
    )
    (net (code "107") (name "unconnected-(U2-NC-Pad59)") (class "Default")
      (node (ref "U2") (pin "59") (pinfunction "NC_59") (pintype "no_connect"))
    )
    (net (code "108") (name "unconnected-(U2-NC-Pad63)") (class "Default")
      (node (ref "U2") (pin "63") (pinfunction "NC_63") (pintype "no_connect"))
    )
    (net (code "109") (name "unconnected-(U5-NC-Pad27)") (class "Default")
      (node (ref "U5") (pin "27") (pinfunction "NC_27") (pintype "bidirectional"))
    )
    (net (code "110") (name "unconnected-(U5-REFIN-Pad14)") (class "Default")
      (node (ref "U5") (pin "14") (pinfunction "REFIN_14") (pintype "input"))
    )
  )
)
